# vstupy.net
KiCad netlist of a schematic drawn in EAGLE
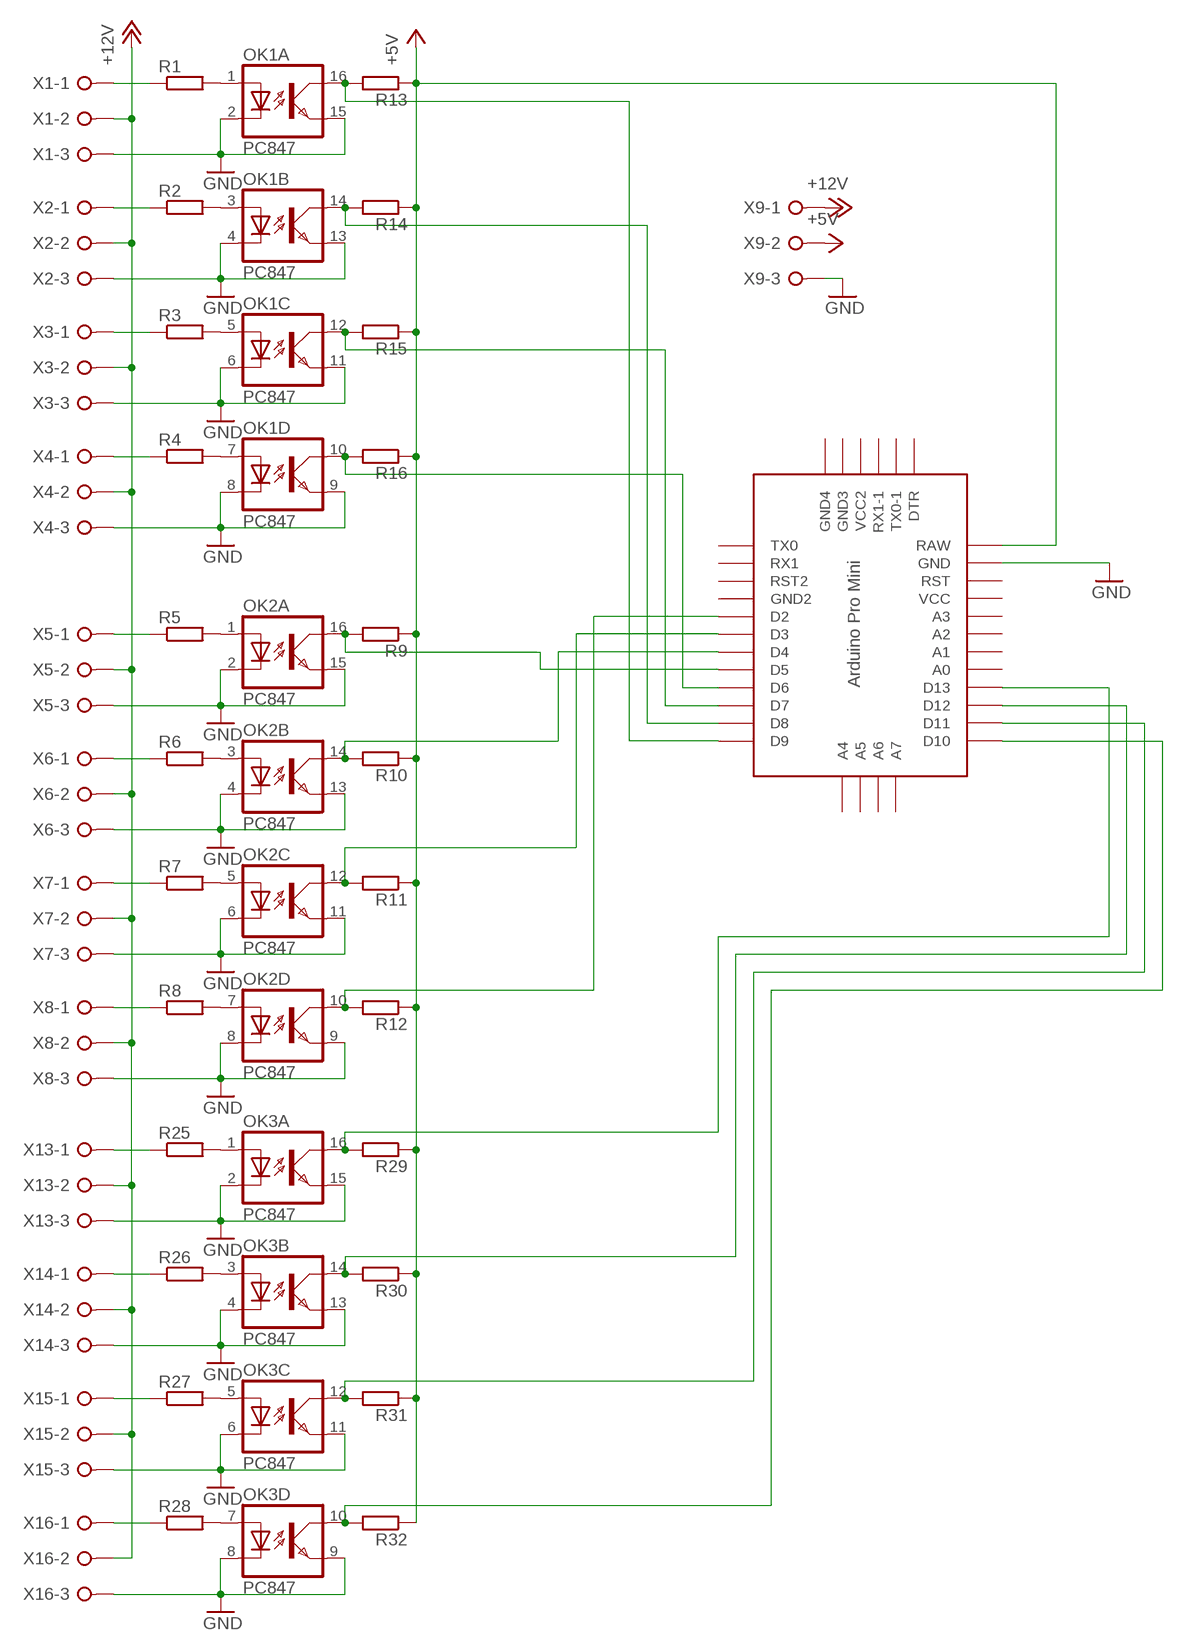
[diagram p0: schematic, sheet 1]

(export (version "E")
  (design (tool "Eeschema 10.0.6"))
  (components
    (comp (ref "OK1")
      (value "PC847")
      (footprint "eagle-import:DIL16")
      (libsource (lib "eagle-import") (part "PC847"))
    )
    (comp (ref "OK2")
      (value "PC847")
      (footprint "eagle-import:DIL16")
      (libsource (lib "eagle-import") (part "PC847"))
    )
    (comp (ref "OK3")
      (value "PC847")
      (footprint "eagle-import:DIL16")
      (libsource (lib "eagle-import") (part "PC847"))
    )
    (comp (ref "R1")
      (value "R-EU_0204/5")
      (footprint "eagle-import:0204_5")
      (libsource (lib "eagle-import") (part "R-EU_0204/5"))
    )
    (comp (ref "R2")
      (value "R-EU_0204/5")
      (footprint "eagle-import:0204_5")
      (libsource (lib "eagle-import") (part "R-EU_0204/5"))
    )
    (comp (ref "R3")
      (value "R-EU_0204/5")
      (footprint "eagle-import:0204_5")
      (libsource (lib "eagle-import") (part "R-EU_0204/5"))
    )
    (comp (ref "R4")
      (value "R-EU_0204/5")
      (footprint "eagle-import:0204_5")
      (libsource (lib "eagle-import") (part "R-EU_0204/5"))
    )
    (comp (ref "R5")
      (value "R-EU_0204/5")
      (footprint "eagle-import:0204_5")
      (libsource (lib "eagle-import") (part "R-EU_0204/5"))
    )
    (comp (ref "R6")
      (value "R-EU_0204/5")
      (footprint "eagle-import:0204_5")
      (libsource (lib "eagle-import") (part "R-EU_0204/5"))
    )
    (comp (ref "R7")
      (value "R-EU_0204/5")
      (footprint "eagle-import:0204_5")
      (libsource (lib "eagle-import") (part "R-EU_0204/5"))
    )
    (comp (ref "R8")
      (value "R-EU_0204/5")
      (footprint "eagle-import:0204_5")
      (libsource (lib "eagle-import") (part "R-EU_0204/5"))
    )
    (comp (ref "R9")
      (value "R-EU_0204/5")
      (footprint "eagle-import:0204_5")
      (libsource (lib "eagle-import") (part "R-EU_0204/5"))
    )
    (comp (ref "R10")
      (value "R-EU_0204/5")
      (footprint "eagle-import:0204_5")
      (libsource (lib "eagle-import") (part "R-EU_0204/5"))
    )
    (comp (ref "R11")
      (value "R-EU_0204/5")
      (footprint "eagle-import:0204_5")
      (libsource (lib "eagle-import") (part "R-EU_0204/5"))
    )
    (comp (ref "R12")
      (value "R-EU_0204/5")
      (footprint "eagle-import:0204_5")
      (libsource (lib "eagle-import") (part "R-EU_0204/5"))
    )
    (comp (ref "R13")
      (value "R-EU_0204/5")
      (footprint "eagle-import:0204_5")
      (libsource (lib "eagle-import") (part "R-EU_0204/5"))
    )
    (comp (ref "R14")
      (value "R-EU_0204/5")
      (footprint "eagle-import:0204_5")
      (libsource (lib "eagle-import") (part "R-EU_0204/5"))
    )
    (comp (ref "R15")
      (value "R-EU_0204/5")
      (footprint "eagle-import:0204_5")
      (libsource (lib "eagle-import") (part "R-EU_0204/5"))
    )
    (comp (ref "R16")
      (value "R-EU_0204/5")
      (footprint "eagle-import:0204_5")
      (libsource (lib "eagle-import") (part "R-EU_0204/5"))
    )
    (comp (ref "R25")
      (value "R-EU_0204/5")
      (footprint "eagle-import:0204_5")
      (libsource (lib "eagle-import") (part "R-EU_0204/5"))
    )
    (comp (ref "R26")
      (value "R-EU_0204/5")
      (footprint "eagle-import:0204_5")
      (libsource (lib "eagle-import") (part "R-EU_0204/5"))
    )
    (comp (ref "R27")
      (value "R-EU_0204/5")
      (footprint "eagle-import:0204_5")
      (libsource (lib "eagle-import") (part "R-EU_0204/5"))
    )
    (comp (ref "R28")
      (value "R-EU_0204/5")
      (footprint "eagle-import:0204_5")
      (libsource (lib "eagle-import") (part "R-EU_0204/5"))
    )
    (comp (ref "R29")
      (value "R-EU_0204/5")
      (footprint "eagle-import:0204_5")
      (libsource (lib "eagle-import") (part "R-EU_0204/5"))
    )
    (comp (ref "R30")
      (value "R-EU_0204/5")
      (footprint "eagle-import:0204_5")
      (libsource (lib "eagle-import") (part "R-EU_0204/5"))
    )
    (comp (ref "R31")
      (value "R-EU_0204/5")
      (footprint "eagle-import:0204_5")
      (libsource (lib "eagle-import") (part "R-EU_0204/5"))
    )
    (comp (ref "R32")
      (value "R-EU_0204/5")
      (footprint "eagle-import:0204_5")
      (libsource (lib "eagle-import") (part "R-EU_0204/5"))
    )
    (comp (ref "U$1")
      (value "PRO-MINI")
      (footprint "eagle-import:PRO-MINI")
      (libsource (lib "eagle-import") (part "PRO-MINI"))
    )
    (comp (ref "X1")
      (value "W237-3E")
      (footprint "eagle-import:W237-3E")
      (libsource (lib "eagle-import") (part "W237-3E"))
    )
    (comp (ref "X2")
      (value "W237-3E")
      (footprint "eagle-import:W237-3E")
      (libsource (lib "eagle-import") (part "W237-3E"))
    )
    (comp (ref "X3")
      (value "W237-3E")
      (footprint "eagle-import:W237-3E")
      (libsource (lib "eagle-import") (part "W237-3E"))
    )
    (comp (ref "X4")
      (value "W237-3E")
      (footprint "eagle-import:W237-3E")
      (libsource (lib "eagle-import") (part "W237-3E"))
    )
    (comp (ref "X5")
      (value "W237-3E")
      (footprint "eagle-import:W237-3E")
      (libsource (lib "eagle-import") (part "W237-3E"))
    )
    (comp (ref "X6")
      (value "W237-3E")
      (footprint "eagle-import:W237-3E")
      (libsource (lib "eagle-import") (part "W237-3E"))
    )
    (comp (ref "X7")
      (value "W237-3E")
      (footprint "eagle-import:W237-3E")
      (libsource (lib "eagle-import") (part "W237-3E"))
    )
    (comp (ref "X8")
      (value "W237-3E")
      (footprint "eagle-import:W237-3E")
      (libsource (lib "eagle-import") (part "W237-3E"))
    )
    (comp (ref "X9")
      (value "W237-3E")
      (footprint "eagle-import:W237-3E")
      (libsource (lib "eagle-import") (part "W237-3E"))
    )
    (comp (ref "X13")
      (value "W237-3E")
      (footprint "eagle-import:W237-3E")
      (libsource (lib "eagle-import") (part "W237-3E"))
    )
    (comp (ref "X14")
      (value "W237-3E")
      (footprint "eagle-import:W237-3E")
      (libsource (lib "eagle-import") (part "W237-3E"))
    )
    (comp (ref "X15")
      (value "W237-3E")
      (footprint "eagle-import:W237-3E")
      (libsource (lib "eagle-import") (part "W237-3E"))
    )
    (comp (ref "X16")
      (value "W237-3E")
      (footprint "eagle-import:W237-3E")
      (libsource (lib "eagle-import") (part "W237-3E"))
    )
  )
  (nets
    (net (code "1") (name "+5V") (class "Default")
      (node (ref "R10") (pin "1") (pinfunction "1_1") (pintype "passive"))
      (node (ref "R11") (pin "1") (pinfunction "1_1") (pintype "passive"))
      (node (ref "R12") (pin "1") (pinfunction "1_1") (pintype "passive"))
      (node (ref "R13") (pin "1") (pinfunction "1_1") (pintype "passive"))
      (node (ref "R14") (pin "1") (pinfunction "1_1") (pintype "passive"))
      (node (ref "R15") (pin "1") (pinfunction "1_1") (pintype "passive"))
      (node (ref "R16") (pin "1") (pinfunction "1_1") (pintype "passive"))
      (node (ref "R29") (pin "1") (pinfunction "1_1") (pintype "passive"))
      (node (ref "R30") (pin "1") (pinfunction "1_1") (pintype "passive"))
      (node (ref "R31") (pin "1") (pinfunction "1_1") (pintype "passive"))
      (node (ref "R32") (pin "1") (pinfunction "1_1") (pintype "passive"))
      (node (ref "R9") (pin "1") (pinfunction "1_1") (pintype "passive"))
      (node (ref "U$1") (pin "RAW") (pinfunction "RAW_RAW") (pintype "power_in"))
      (node (ref "X9") (pin "2") (pinfunction "KL_2") (pintype "passive"))
    )
    (net (code "2") (name "+12V") (class "Default")
      (node (ref "X1") (pin "2") (pinfunction "KL_2") (pintype "passive"))
      (node (ref "X13") (pin "2") (pinfunction "KL_2") (pintype "passive"))
      (node (ref "X14") (pin "2") (pinfunction "KL_2") (pintype "passive"))
      (node (ref "X15") (pin "2") (pinfunction "KL_2") (pintype "passive"))
      (node (ref "X16") (pin "2") (pinfunction "KL_2") (pintype "passive"))
      (node (ref "X2") (pin "2") (pinfunction "KL_2") (pintype "passive"))
      (node (ref "X3") (pin "2") (pinfunction "KL_2") (pintype "passive"))
      (node (ref "X4") (pin "2") (pinfunction "KL_2") (pintype "passive"))
      (node (ref "X5") (pin "2") (pinfunction "KL_2") (pintype "passive"))
      (node (ref "X6") (pin "2") (pinfunction "KL_2") (pintype "passive"))
      (node (ref "X7") (pin "2") (pinfunction "KL_2") (pintype "passive"))
      (node (ref "X8") (pin "2") (pinfunction "KL_2") (pintype "passive"))
      (node (ref "X9") (pin "1") (pinfunction "KL_1") (pintype "passive"))
    )
    (net (code "3") (name "GND") (class "Default")
      (node (ref "OK1") (pin "11") (pinfunction "EMIT_11") (pintype "passive"))
      (node (ref "OK1") (pin "13") (pinfunction "EMIT_13") (pintype "passive"))
      (node (ref "OK1") (pin "15") (pinfunction "EMIT_15") (pintype "passive"))
      (node (ref "OK1") (pin "2") (pinfunction "C_2") (pintype "passive"))
      (node (ref "OK1") (pin "4") (pinfunction "C_4") (pintype "passive"))
      (node (ref "OK1") (pin "6") (pinfunction "C_6") (pintype "passive"))
      (node (ref "OK1") (pin "8") (pinfunction "C_8") (pintype "passive"))
      (node (ref "OK1") (pin "9") (pinfunction "EMIT_9") (pintype "passive"))
      (node (ref "OK2") (pin "11") (pinfunction "EMIT_11") (pintype "passive"))
      (node (ref "OK2") (pin "13") (pinfunction "EMIT_13") (pintype "passive"))
      (node (ref "OK2") (pin "15") (pinfunction "EMIT_15") (pintype "passive"))
      (node (ref "OK2") (pin "2") (pinfunction "C_2") (pintype "passive"))
      (node (ref "OK2") (pin "4") (pinfunction "C_4") (pintype "passive"))
      (node (ref "OK2") (pin "6") (pinfunction "C_6") (pintype "passive"))
      (node (ref "OK2") (pin "8") (pinfunction "C_8") (pintype "passive"))
      (node (ref "OK2") (pin "9") (pinfunction "EMIT_9") (pintype "passive"))
      (node (ref "OK3") (pin "11") (pinfunction "EMIT_11") (pintype "passive"))
      (node (ref "OK3") (pin "13") (pinfunction "EMIT_13") (pintype "passive"))
      (node (ref "OK3") (pin "15") (pinfunction "EMIT_15") (pintype "passive"))
      (node (ref "OK3") (pin "2") (pinfunction "C_2") (pintype "passive"))
      (node (ref "OK3") (pin "4") (pinfunction "C_4") (pintype "passive"))
      (node (ref "OK3") (pin "6") (pinfunction "C_6") (pintype "passive"))
      (node (ref "OK3") (pin "8") (pinfunction "C_8") (pintype "passive"))
      (node (ref "OK3") (pin "9") (pinfunction "EMIT_9") (pintype "passive"))
      (node (ref "U$1") (pin "GND") (pinfunction "GND_GND") (pintype "input"))
      (node (ref "X1") (pin "3") (pinfunction "KL_3") (pintype "passive"))
      (node (ref "X13") (pin "3") (pinfunction "KL_3") (pintype "passive"))
      (node (ref "X14") (pin "3") (pinfunction "KL_3") (pintype "passive"))
      (node (ref "X15") (pin "3") (pinfunction "KL_3") (pintype "passive"))
      (node (ref "X16") (pin "3") (pinfunction "KL_3") (pintype "passive"))
      (node (ref "X2") (pin "3") (pinfunction "KL_3") (pintype "passive"))
      (node (ref "X3") (pin "3") (pinfunction "KL_3") (pintype "passive"))
      (node (ref "X4") (pin "3") (pinfunction "KL_3") (pintype "passive"))
      (node (ref "X5") (pin "3") (pinfunction "KL_3") (pintype "passive"))
      (node (ref "X6") (pin "3") (pinfunction "KL_3") (pintype "passive"))
      (node (ref "X7") (pin "3") (pinfunction "KL_3") (pintype "passive"))
      (node (ref "X8") (pin "3") (pinfunction "KL_3") (pintype "passive"))
      (node (ref "X9") (pin "3") (pinfunction "KL_3") (pintype "passive"))
    )
    (net (code "4") (name "Net-(OK1A-A)") (class "Default")
      (node (ref "OK1") (pin "1") (pinfunction "A_1") (pintype "passive"))
      (node (ref "R1") (pin "2") (pinfunction "2_2") (pintype "passive"))
    )
    (net (code "5") (name "Net-(OK1A-COL)") (class "Default")
      (node (ref "OK1") (pin "16") (pinfunction "COL_16") (pintype "passive"))
      (node (ref "R13") (pin "2") (pinfunction "2_2") (pintype "passive"))
      (node (ref "U$1") (pin "D9") (pinfunction "D9_D9") (pintype "bidirectional"))
    )
    (net (code "6") (name "Net-(OK1B-A)") (class "Default")
      (node (ref "OK1") (pin "3") (pinfunction "A_3") (pintype "passive"))
      (node (ref "R2") (pin "2") (pinfunction "2_2") (pintype "passive"))
    )
    (net (code "7") (name "Net-(OK1B-COL)") (class "Default")
      (node (ref "OK1") (pin "14") (pinfunction "COL_14") (pintype "passive"))
      (node (ref "R14") (pin "2") (pinfunction "2_2") (pintype "passive"))
      (node (ref "U$1") (pin "D8") (pinfunction "D8_D8") (pintype "bidirectional"))
    )
    (net (code "8") (name "Net-(OK1C-A)") (class "Default")
      (node (ref "OK1") (pin "5") (pinfunction "A_5") (pintype "passive"))
      (node (ref "R3") (pin "2") (pinfunction "2_2") (pintype "passive"))
    )
    (net (code "9") (name "Net-(OK1C-COL)") (class "Default")
      (node (ref "OK1") (pin "12") (pinfunction "COL_12") (pintype "passive"))
      (node (ref "R15") (pin "2") (pinfunction "2_2") (pintype "passive"))
      (node (ref "U$1") (pin "D7") (pinfunction "D7_D7") (pintype "bidirectional"))
    )
    (net (code "10") (name "Net-(OK1D-A)") (class "Default")
      (node (ref "OK1") (pin "7") (pinfunction "A_7") (pintype "passive"))
      (node (ref "R4") (pin "2") (pinfunction "2_2") (pintype "passive"))
    )
    (net (code "11") (name "Net-(OK1D-COL)") (class "Default")
      (node (ref "OK1") (pin "10") (pinfunction "COL_10") (pintype "passive"))
      (node (ref "R16") (pin "2") (pinfunction "2_2") (pintype "passive"))
      (node (ref "U$1") (pin "D6") (pinfunction "D6_D6") (pintype "bidirectional"))
    )
    (net (code "12") (name "Net-(OK2A-A)") (class "Default")
      (node (ref "OK2") (pin "1") (pinfunction "A_1") (pintype "passive"))
      (node (ref "R5") (pin "2") (pinfunction "2_2") (pintype "passive"))
    )
    (net (code "13") (name "Net-(OK2A-COL)") (class "Default")
      (node (ref "OK2") (pin "16") (pinfunction "COL_16") (pintype "passive"))
      (node (ref "R9") (pin "2") (pinfunction "2_2") (pintype "passive"))
      (node (ref "U$1") (pin "D5") (pinfunction "D5_D5") (pintype "bidirectional"))
    )
    (net (code "14") (name "Net-(OK2B-A)") (class "Default")
      (node (ref "OK2") (pin "3") (pinfunction "A_3") (pintype "passive"))
      (node (ref "R6") (pin "2") (pinfunction "2_2") (pintype "passive"))
    )
    (net (code "15") (name "Net-(OK2B-COL)") (class "Default")
      (node (ref "OK2") (pin "14") (pinfunction "COL_14") (pintype "passive"))
      (node (ref "R10") (pin "2") (pinfunction "2_2") (pintype "passive"))
      (node (ref "U$1") (pin "D4") (pinfunction "D4_D4") (pintype "bidirectional"))
    )
    (net (code "16") (name "Net-(OK2C-A)") (class "Default")
      (node (ref "OK2") (pin "5") (pinfunction "A_5") (pintype "passive"))
      (node (ref "R7") (pin "2") (pinfunction "2_2") (pintype "passive"))
    )
    (net (code "17") (name "Net-(OK2C-COL)") (class "Default")
      (node (ref "OK2") (pin "12") (pinfunction "COL_12") (pintype "passive"))
      (node (ref "R11") (pin "2") (pinfunction "2_2") (pintype "passive"))
      (node (ref "U$1") (pin "D3") (pinfunction "D3_D3") (pintype "bidirectional"))
    )
    (net (code "18") (name "Net-(OK2D-A)") (class "Default")
      (node (ref "OK2") (pin "7") (pinfunction "A_7") (pintype "passive"))
      (node (ref "R8") (pin "2") (pinfunction "2_2") (pintype "passive"))
    )
    (net (code "19") (name "Net-(OK2D-COL)") (class "Default")
      (node (ref "OK2") (pin "10") (pinfunction "COL_10") (pintype "passive"))
      (node (ref "R12") (pin "2") (pinfunction "2_2") (pintype "passive"))
      (node (ref "U$1") (pin "D2") (pinfunction "D2_D2") (pintype "bidirectional"))
    )
    (net (code "20") (name "Net-(OK3A-A)") (class "Default")
      (node (ref "OK3") (pin "1") (pinfunction "A_1") (pintype "passive"))
      (node (ref "R25") (pin "2") (pinfunction "2_2") (pintype "passive"))
    )
    (net (code "21") (name "Net-(OK3A-COL)") (class "Default")
      (node (ref "OK3") (pin "16") (pinfunction "COL_16") (pintype "passive"))
      (node (ref "R29") (pin "2") (pinfunction "2_2") (pintype "passive"))
      (node (ref "U$1") (pin "D13") (pinfunction "D13_D13") (pintype "bidirectional"))
    )
    (net (code "22") (name "Net-(OK3B-A)") (class "Default")
      (node (ref "OK3") (pin "3") (pinfunction "A_3") (pintype "passive"))
      (node (ref "R26") (pin "2") (pinfunction "2_2") (pintype "passive"))
    )
    (net (code "23") (name "Net-(OK3B-COL)") (class "Default")
      (node (ref "OK3") (pin "14") (pinfunction "COL_14") (pintype "passive"))
      (node (ref "R30") (pin "2") (pinfunction "2_2") (pintype "passive"))
      (node (ref "U$1") (pin "D12") (pinfunction "D12_D12") (pintype "bidirectional"))
    )
    (net (code "24") (name "Net-(OK3C-A)") (class "Default")
      (node (ref "OK3") (pin "5") (pinfunction "A_5") (pintype "passive"))
      (node (ref "R27") (pin "2") (pinfunction "2_2") (pintype "passive"))
    )
    (net (code "25") (name "Net-(OK3C-COL)") (class "Default")
      (node (ref "OK3") (pin "12") (pinfunction "COL_12") (pintype "passive"))
      (node (ref "R31") (pin "2") (pinfunction "2_2") (pintype "passive"))
      (node (ref "U$1") (pin "D11") (pinfunction "D11_D11") (pintype "bidirectional"))
    )
    (net (code "26") (name "Net-(OK3D-A)") (class "Default")
      (node (ref "OK3") (pin "7") (pinfunction "A_7") (pintype "passive"))
      (node (ref "R28") (pin "2") (pinfunction "2_2") (pintype "passive"))
    )
    (net (code "27") (name "Net-(OK3D-COL)") (class "Default")
      (node (ref "OK3") (pin "10") (pinfunction "COL_10") (pintype "passive"))
      (node (ref "R32") (pin "2") (pinfunction "2_2") (pintype "passive"))
      (node (ref "U$1") (pin "D10") (pinfunction "D10_D10") (pintype "bidirectional"))
    )
    (net (code "28") (name "Net-(X1A-KL)") (class "Default")
      (node (ref "R1") (pin "1") (pinfunction "1_1") (pintype "passive"))
      (node (ref "X1") (pin "1") (pinfunction "KL_1") (pintype "passive"))
    )
    (net (code "29") (name "Net-(X2A-KL)") (class "Default")
      (node (ref "R2") (pin "1") (pinfunction "1_1") (pintype "passive"))
      (node (ref "X2") (pin "1") (pinfunction "KL_1") (pintype "passive"))
    )
    (net (code "30") (name "Net-(X3A-KL)") (class "Default")
      (node (ref "R3") (pin "1") (pinfunction "1_1") (pintype "passive"))
      (node (ref "X3") (pin "1") (pinfunction "KL_1") (pintype "passive"))
    )
    (net (code "31") (name "Net-(X4A-KL)") (class "Default")
      (node (ref "R4") (pin "1") (pinfunction "1_1") (pintype "passive"))
      (node (ref "X4") (pin "1") (pinfunction "KL_1") (pintype "passive"))
    )
    (net (code "32") (name "Net-(X5A-KL)") (class "Default")
      (node (ref "R5") (pin "1") (pinfunction "1_1") (pintype "passive"))
      (node (ref "X5") (pin "1") (pinfunction "KL_1") (pintype "passive"))
    )
    (net (code "33") (name "Net-(X6A-KL)") (class "Default")
      (node (ref "R6") (pin "1") (pinfunction "1_1") (pintype "passive"))
      (node (ref "X6") (pin "1") (pinfunction "KL_1") (pintype "passive"))
    )
    (net (code "34") (name "Net-(X7A-KL)") (class "Default")
      (node (ref "R7") (pin "1") (pinfunction "1_1") (pintype "passive"))
      (node (ref "X7") (pin "1") (pinfunction "KL_1") (pintype "passive"))
    )
    (net (code "35") (name "Net-(X8A-KL)") (class "Default")
      (node (ref "R8") (pin "1") (pinfunction "1_1") (pintype "passive"))
      (node (ref "X8") (pin "1") (pinfunction "KL_1") (pintype "passive"))
    )
    (net (code "36") (name "Net-(X13A-KL)") (class "Default")
      (node (ref "R25") (pin "1") (pinfunction "1_1") (pintype "passive"))
      (node (ref "X13") (pin "1") (pinfunction "KL_1") (pintype "passive"))
    )
    (net (code "37") (name "Net-(X14A-KL)") (class "Default")
      (node (ref "R26") (pin "1") (pinfunction "1_1") (pintype "passive"))
      (node (ref "X14") (pin "1") (pinfunction "KL_1") (pintype "passive"))
    )
    (net (code "38") (name "Net-(X15A-KL)") (class "Default")
      (node (ref "R27") (pin "1") (pinfunction "1_1") (pintype "passive"))
      (node (ref "X15") (pin "1") (pinfunction "KL_1") (pintype "passive"))
    )
    (net (code "39") (name "Net-(X16A-KL)") (class "Default")
      (node (ref "R28") (pin "1") (pinfunction "1_1") (pintype "passive"))
      (node (ref "X16") (pin "1") (pinfunction "KL_1") (pintype "passive"))
    )
    (net (code "40") (name "unconnected-(U$1-GND2-PadGND1)") (class "Default")
      (node (ref "U$1") (pin "GND1") (pinfunction "GND2_GND1") (pintype "bidirectional"))
    )
    (net (code "41") (name "unconnected-(U$1-GND4-PadGND2)") (class "Default")
      (node (ref "U$1") (pin "GND2") (pinfunction "GND4_GND2") (pintype "bidirectional"))
    )
    (net (code "42") (name "unconnected-(U$1-PadA0)") (class "Default")
      (node (ref "U$1") (pin "A0") (pinfunction "A0_A0") (pintype "bidirectional"))
    )
    (net (code "43") (name "unconnected-(U$1-PadA1)") (class "Default")
      (node (ref "U$1") (pin "A1") (pinfunction "A1_A1") (pintype "bidirectional"))
    )
    (net (code "44") (name "unconnected-(U$1-PadA2)") (class "Default")
      (node (ref "U$1") (pin "A2") (pinfunction "A2_A2") (pintype "bidirectional"))
    )
    (net (code "45") (name "unconnected-(U$1-PadA3)") (class "Default")
      (node (ref "U$1") (pin "A3") (pinfunction "A3_A3") (pintype "bidirectional"))
    )
    (net (code "46") (name "unconnected-(U$1-PadA4)") (class "Default")
      (node (ref "U$1") (pin "A4") (pinfunction "A4_A4") (pintype "bidirectional"))
    )
    (net (code "47") (name "unconnected-(U$1-PadA5)") (class "Default")
      (node (ref "U$1") (pin "A5") (pinfunction "A5_A5") (pintype "bidirectional"))
    )
    (net (code "48") (name "unconnected-(U$1-PadA6)") (class "Default")
      (node (ref "U$1") (pin "A6") (pinfunction "A6_A6") (pintype "bidirectional"))
    )
    (net (code "49") (name "unconnected-(U$1-PadA7)") (class "Default")
      (node (ref "U$1") (pin "A7") (pinfunction "A7_A7") (pintype "bidirectional"))
    )
    (net (code "50") (name "unconnected-(U$1-PadDTR)") (class "Default")
      (node (ref "U$1") (pin "DTR") (pinfunction "DTR_DTR") (pintype "bidirectional"))
    )
    (net (code "51") (name "unconnected-(U$1-PadGND3)") (class "Default")
      (node (ref "U$1") (pin "GND3") (pinfunction "GND3_GND3") (pintype "bidirectional"))
    )
    (net (code "52") (name "unconnected-(U$1-PadRST)") (class "Default")
      (node (ref "U$1") (pin "RST") (pinfunction "RST_RST") (pintype "bidirectional"))
    )
    (net (code "53") (name "unconnected-(U$1-PadRX1)") (class "Default")
      (node (ref "U$1") (pin "RX1") (pinfunction "RX1_RX1") (pintype "bidirectional"))
    )
    (net (code "54") (name "unconnected-(U$1-PadRX1-1)") (class "Default")
      (node (ref "U$1") (pin "RX1-1") (pinfunction "RX1-1_RX1-1") (pintype "bidirectional"))
    )
    (net (code "55") (name "unconnected-(U$1-PadTX0)") (class "Default")
      (node (ref "U$1") (pin "TX0") (pinfunction "TX0_TX0") (pintype "bidirectional"))
    )
    (net (code "56") (name "unconnected-(U$1-PadTX0-1)") (class "Default")
      (node (ref "U$1") (pin "TX0-1") (pinfunction "TX0-1_TX0-1") (pintype "bidirectional"))
    )
    (net (code "57") (name "unconnected-(U$1-PadVCC)") (class "Default")
      (node (ref "U$1") (pin "VCC") (pinfunction "VCC_VCC") (pintype "bidirectional"))
    )
    (net (code "58") (name "unconnected-(U$1-RST2-PadRST1)") (class "Default")
      (node (ref "U$1") (pin "RST1") (pinfunction "RST2_RST1") (pintype "bidirectional"))
    )
    (net (code "59") (name "unconnected-(U$1-VCC2-PadVCC1)") (class "Default")
      (node (ref "U$1") (pin "VCC1") (pinfunction "VCC2_VCC1") (pintype "bidirectional"))
    )
  )
)
